# PCB_Agrosavia.net
KiCad netlist of a schematic drawn in EAGLE
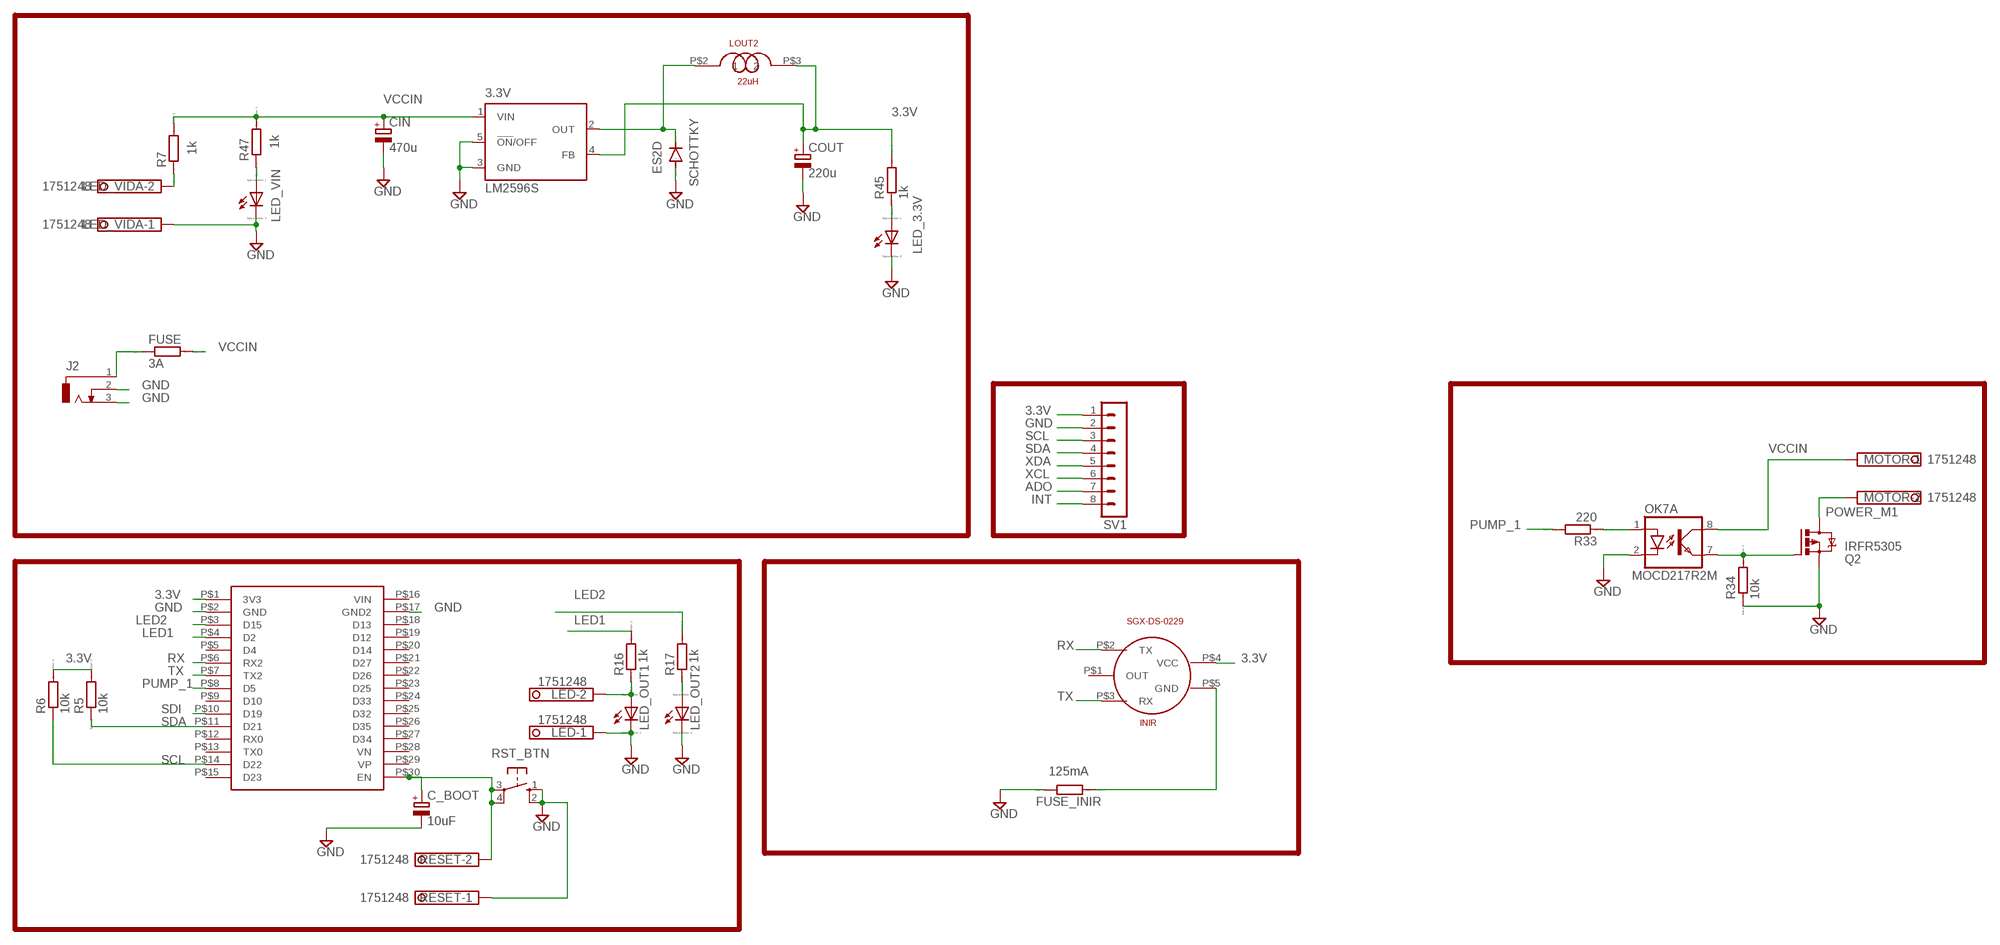
[diagram p0: schematic, sheet 1]

(export (version "E")
  (design (tool "Eeschema 10.0.6"))
  (components
    (comp (ref "3.3V")
      (value "LM2596S")
      (footprint "eagle-import:TO263-5")
      (fields (field (name "MF") "NATIONAL SEMICONDUCTOR") (field (name "MPN") "LM2596S-ADJ/NOPB"))
      (libsource (lib "eagle-import") (part "LM2596S"))
    )
    (comp (ref "CIN")
      (value "470u")
      (footprint "eagle-import:SANYO-OSCON_SMD_F12")
      (libsource (lib "eagle-import") (part "CPOL-EUSANYO_SMD_F12"))
    )
    (comp (ref "COUT")
      (value "220u")
      (footprint "eagle-import:UD-10X10_NICHICON")
      (libsource (lib "eagle-import") (part "CPOL-EUUD-10X10"))
    )
    (comp (ref "C_BOOT")
      (value "10uF")
      (footprint "eagle-import:SANYO-OSCON_SMD_B6")
      (libsource (lib "eagle-import") (part "CPOL-EUSANYO_SMD_B6"))
    )
    (comp (ref "ESP32DEVKITV1")
      (value "ESP32")
      (footprint "eagle-import:ESP32")
      (libsource (lib "eagle-import") (part "ESP32"))
    )
    (comp (ref "FUSE")
      (value "3A")
      (footprint "eagle-import:R1206")
      (libsource (lib "eagle-import") (part "RR1206"))
    )
    (comp (ref "FUSE_INIR")
      (value "125mA")
      (footprint "eagle-import:R0402")
      (libsource (lib "eagle-import") (part "RR0402"))
    )
    (comp (ref "J2")
      (value "DCJ0303")
      (footprint "eagle-import:DCJ0303")
      (libsource (lib "eagle-import") (part "DCJ0303"))
    )
    (comp (ref "LED")
      (value "1751248")
      (footprint "eagle-import:1751248")
      (libsource (lib "eagle-import") (part "1751248"))
    )
    (comp (ref "LED_3.3V")
      (value "LED_E")
      (footprint "eagle-import:LED_1206")
      (libsource (lib "eagle-import") (part "LED_E"))
    )
    (comp (ref "LED_OUT1")
      (value "LED_E")
      (footprint "eagle-import:LED_1206")
      (libsource (lib "eagle-import") (part "LED_E"))
    )
    (comp (ref "LED_OUT2")
      (value "LED_E")
      (footprint "eagle-import:LED_1206")
      (libsource (lib "eagle-import") (part "LED_E"))
    )
    (comp (ref "LED_VIDA")
      (value "1751248")
      (footprint "eagle-import:1751248")
      (libsource (lib "eagle-import") (part "1751248"))
    )
    (comp (ref "LED_VIN")
      (value "LED_E")
      (footprint "eagle-import:LED_1206")
      (libsource (lib "eagle-import") (part "LED_E"))
    )
    (comp (ref "LOUT2")
      (value "22uH")
      (footprint "eagle-import:SRP1038A")
      (libsource (lib "eagle-import") (part "SRP1038A"))
    )
    (comp (ref "MOTOR")
      (value "1751248")
      (footprint "eagle-import:1751248")
      (libsource (lib "eagle-import") (part "1751248"))
    )
    (comp (ref "OK7")
      (value "MOCD217R2M")
      (footprint "eagle-import:SOIC08")
      (fields (field (name "MF") "VISHAY/TELEFUNKEN") (field (name "MPN") "ILD205T"))
      (libsource (lib "eagle-import") (part "ILD205"))
    )
    (comp (ref "Q2")
      (value "IRFR5305")
      (footprint "eagle-import:D-PAK_TO252AA")
      (libsource (lib "eagle-import") (part "IRF?5305R"))
    )
    (comp (ref "R5")
      (value "10k")
      (footprint "eagle-import:R1206")
      (libsource (lib "eagle-import") (part "RR1206"))
    )
    (comp (ref "R6")
      (value "10k")
      (footprint "eagle-import:R1206")
      (libsource (lib "eagle-import") (part "RR1206"))
    )
    (comp (ref "R7")
      (value "1k")
      (footprint "eagle-import:R0805")
      (libsource (lib "eagle-import") (part "R"))
    )
    (comp (ref "R16")
      (value "1k")
      (footprint "eagle-import:R0805")
      (libsource (lib "eagle-import") (part "R"))
    )
    (comp (ref "R17")
      (value "1k")
      (footprint "eagle-import:R0805")
      (libsource (lib "eagle-import") (part "R"))
    )
    (comp (ref "R33")
      (value "220")
      (footprint "eagle-import:R0603")
      (libsource (lib "eagle-import") (part "RR0603"))
    )
    (comp (ref "R34")
      (value "10k")
      (footprint "eagle-import:R1206")
      (libsource (lib "eagle-import") (part "RR1206"))
    )
    (comp (ref "R45")
      (value "1k")
      (footprint "eagle-import:R0805")
      (libsource (lib "eagle-import") (part "R"))
    )
    (comp (ref "R47")
      (value "1k")
      (footprint "eagle-import:R0805")
      (libsource (lib "eagle-import") (part "R"))
    )
    (comp (ref "RESET")
      (value "1751248")
      (footprint "eagle-import:1751248")
      (libsource (lib "eagle-import") (part "1751248"))
    )
    (comp (ref "RST_BTN")
      (value "10-XX")
      (footprint "eagle-import:B3F-10XX")
      (fields (field (name "MPN") "B3F-1000"))
      (libsource (lib "eagle-import") (part "10-XX"))
    )
    (comp (ref "SCHOTTKY")
      (value "ES2D")
      (footprint "eagle-import:SMB")
      (libsource (lib "eagle-import") (part "ES2D"))
    )
    (comp (ref "SGX-DS-0229")
      (value "INIR")
      (footprint "eagle-import:INIR")
      (libsource (lib "eagle-import") (part "INIR"))
    )
    (comp (ref "SV1")
      (value "MA08-1")
      (footprint "eagle-import:MA08-1")
      (libsource (lib "eagle-import") (part "MA08-1"))
    )
  )
  (nets
    (net (code "1") (name "/3.3V") (class "Default")
      (node (ref "3.3V") (pin "4") (pinfunction "FB_4") (pintype "input"))
      (node (ref "COUT") (pin "+") (pinfunction "+_+") (pintype "passive"))
      (node (ref "ESP32DEVKITV1") (pin "P$1") (pinfunction "3V3_P$1") (pintype "bidirectional"))
      (node (ref "LOUT2") (pin "P$3") (pinfunction "2_P$3") (pintype "bidirectional"))
      (node (ref "R45") (pin "2") (pinfunction "2_2") (pintype "passive"))
      (node (ref "R5") (pin "2") (pinfunction "2_2") (pintype "passive"))
      (node (ref "R6") (pin "2") (pinfunction "2_2") (pintype "passive"))
      (node (ref "SGX-DS-0229") (pin "P$4") (pinfunction "VCC_P$4") (pintype "bidirectional"))
      (node (ref "SV1") (pin "1") (pinfunction "1_1") (pintype "passive"))
    )
    (net (code "2") (name "/ADO") (class "Default")
      (node (ref "SV1") (pin "7") (pinfunction "7_7") (pintype "passive"))
    )
    (net (code "3") (name "/INT") (class "Default")
      (node (ref "SV1") (pin "8") (pinfunction "8_8") (pintype "passive"))
    )
    (net (code "4") (name "/LED1") (class "Default")
      (node (ref "ESP32DEVKITV1") (pin "P$4") (pinfunction "D2_P$4") (pintype "bidirectional"))
      (node (ref "R16") (pin "2") (pinfunction "2_2") (pintype "passive"))
    )
    (net (code "5") (name "/LED2") (class "Default")
      (node (ref "ESP32DEVKITV1") (pin "P$3") (pinfunction "D15_P$3") (pintype "bidirectional"))
      (node (ref "R17") (pin "2") (pinfunction "2_2") (pintype "passive"))
    )
    (net (code "6") (name "/POWER_M1") (class "Default")
      (node (ref "MOTOR") (pin "2") (pinfunction "K_2") (pintype "passive"))
      (node (ref "Q2") (pin "4") (pinfunction "D_4") (pintype "passive"))
    )
    (net (code "7") (name "/PUMP_1") (class "Default")
      (node (ref "ESP32DEVKITV1") (pin "P$8") (pinfunction "D5_P$8") (pintype "bidirectional"))
      (node (ref "R33") (pin "2") (pinfunction "2_2") (pintype "passive"))
    )
    (net (code "8") (name "/RX") (class "Default")
      (node (ref "ESP32DEVKITV1") (pin "P$6") (pinfunction "RX2_P$6") (pintype "bidirectional"))
      (node (ref "SGX-DS-0229") (pin "P$2") (pinfunction "TX_P$2") (pintype "bidirectional"))
    )
    (net (code "9") (name "/SCL") (class "Default")
      (node (ref "ESP32DEVKITV1") (pin "P$14") (pinfunction "D22_P$14") (pintype "bidirectional"))
      (node (ref "R6") (pin "1") (pinfunction "1_1") (pintype "passive"))
      (node (ref "SV1") (pin "3") (pinfunction "3_3") (pintype "passive"))
    )
    (net (code "10") (name "/SDA") (class "Default")
      (node (ref "ESP32DEVKITV1") (pin "P$11") (pinfunction "D21_P$11") (pintype "bidirectional"))
      (node (ref "R5") (pin "1") (pinfunction "1_1") (pintype "passive"))
      (node (ref "SV1") (pin "4") (pinfunction "4_4") (pintype "passive"))
    )
    (net (code "11") (name "/SDI") (class "Default")
      (node (ref "ESP32DEVKITV1") (pin "P$10") (pinfunction "D19_P$10") (pintype "bidirectional"))
    )
    (net (code "12") (name "/TX") (class "Default")
      (node (ref "ESP32DEVKITV1") (pin "P$7") (pinfunction "TX2_P$7") (pintype "bidirectional"))
      (node (ref "SGX-DS-0229") (pin "P$3") (pinfunction "RX_P$3") (pintype "bidirectional"))
    )
    (net (code "13") (name "/VCCIN") (class "Default")
      (node (ref "3.3V") (pin "1") (pinfunction "VIN_1") (pintype "input"))
      (node (ref "CIN") (pin "+") (pinfunction "+_+") (pintype "passive"))
      (node (ref "FUSE") (pin "2") (pinfunction "2_2") (pintype "passive"))
      (node (ref "MOTOR") (pin "1") (pinfunction "K_1") (pintype "passive"))
      (node (ref "OK7") (pin "8") (pinfunction "COL_8") (pintype "passive"))
      (node (ref "R47") (pin "2") (pinfunction "2_2") (pintype "passive"))
      (node (ref "R7") (pin "2") (pinfunction "2_2") (pintype "passive"))
    )
    (net (code "14") (name "/XCL") (class "Default")
      (node (ref "SV1") (pin "6") (pinfunction "6_6") (pintype "passive"))
    )
    (net (code "15") (name "/XDA") (class "Default")
      (node (ref "SV1") (pin "5") (pinfunction "5_5") (pintype "passive"))
    )
    (net (code "16") (name "GND") (class "Default")
      (node (ref "3.3V") (pin "3") (pinfunction "GND_3") (pintype "power_in"))
      (node (ref "3.3V") (pin "5") (pinfunction "~{ON}/OFF_5") (pintype "input"))
      (node (ref "CIN") (pin "-") (pinfunction "-_-") (pintype "passive"))
      (node (ref "COUT") (pin "-") (pinfunction "-_-") (pintype "passive"))
      (node (ref "C_BOOT") (pin "-") (pinfunction "-_-") (pintype "passive"))
      (node (ref "ESP32DEVKITV1") (pin "P$17") (pinfunction "GND2_P$17") (pintype "bidirectional"))
      (node (ref "ESP32DEVKITV1") (pin "P$2") (pinfunction "GND_P$2") (pintype "bidirectional"))
      (node (ref "FUSE_INIR") (pin "2") (pinfunction "2_2") (pintype "passive"))
      (node (ref "J2") (pin "2") (pinfunction "2_2") (pintype "passive"))
      (node (ref "J2") (pin "3") (pinfunction "3_3") (pintype "passive"))
      (node (ref "LED") (pin "1") (pinfunction "K_1") (pintype "passive"))
      (node (ref "LED_3.3V") (pin "C") (pinfunction "C_C") (pintype "passive"))
      (node (ref "LED_OUT1") (pin "C") (pinfunction "C_C") (pintype "passive"))
      (node (ref "LED_OUT2") (pin "C") (pinfunction "C_C") (pintype "passive"))
      (node (ref "LED_VIDA") (pin "1") (pinfunction "K_1") (pintype "passive"))
      (node (ref "LED_VIN") (pin "C") (pinfunction "C_C") (pintype "passive"))
      (node (ref "OK7") (pin "2") (pinfunction "C_2") (pintype "passive"))
      (node (ref "Q2") (pin "3") (pinfunction "S_3") (pintype "passive"))
      (node (ref "R34") (pin "1") (pinfunction "1_1") (pintype "passive"))
      (node (ref "RESET") (pin "1") (pinfunction "K_1") (pintype "passive"))
      (node (ref "RST_BTN") (pin "1") (pinfunction "S_1") (pintype "passive"))
      (node (ref "RST_BTN") (pin "2") (pinfunction "S1_2") (pintype "passive"))
      (node (ref "SCHOTTKY") (pin "A") (pinfunction "A_A") (pintype "passive"))
      (node (ref "SV1") (pin "2") (pinfunction "2_2") (pintype "passive"))
    )
    (net (code "17") (name "Net-(3.3V-OUT)") (class "Default")
      (node (ref "3.3V") (pin "2") (pinfunction "OUT_2") (pintype "output"))
      (node (ref "LOUT2") (pin "P$2") (pinfunction "1_P$2") (pintype "bidirectional"))
      (node (ref "SCHOTTKY") (pin "C") (pinfunction "C_C") (pintype "passive"))
    )
    (net (code "18") (name "Net-(ESP32DEVKITV1-EN)") (class "Default")
      (node (ref "C_BOOT") (pin "+") (pinfunction "+_+") (pintype "passive"))
      (node (ref "ESP32DEVKITV1") (pin "P$30") (pinfunction "EN_P$30") (pintype "bidirectional"))
      (node (ref "RESET") (pin "2") (pinfunction "K_2") (pintype "passive"))
      (node (ref "RST_BTN") (pin "3") (pinfunction "P_3") (pintype "passive"))
      (node (ref "RST_BTN") (pin "4") (pinfunction "P1_4") (pintype "passive"))
    )
    (net (code "19") (name "Net-(FUSE-Pad1)") (class "Default")
      (node (ref "FUSE") (pin "1") (pinfunction "1_1") (pintype "passive"))
      (node (ref "J2") (pin "1") (pinfunction "1_1") (pintype "passive"))
    )
    (net (code "20") (name "Net-(LEDB-K)") (class "Default")
      (node (ref "LED") (pin "2") (pinfunction "K_2") (pintype "passive"))
      (node (ref "LED_OUT1") (pin "A") (pinfunction "A_A") (pintype "passive"))
      (node (ref "R16") (pin "1") (pinfunction "1_1") (pintype "passive"))
    )
    (net (code "21") (name "Net-(LED_3.3V-PadA)") (class "Default")
      (node (ref "LED_3.3V") (pin "A") (pinfunction "A_A") (pintype "passive"))
      (node (ref "R45") (pin "1") (pinfunction "1_1") (pintype "passive"))
    )
    (net (code "22") (name "Net-(LED_OUT2-PadA)") (class "Default")
      (node (ref "LED_OUT2") (pin "A") (pinfunction "A_A") (pintype "passive"))
      (node (ref "R17") (pin "1") (pinfunction "1_1") (pintype "passive"))
    )
    (net (code "23") (name "Net-(LED_VIDAB-K)") (class "Default")
      (node (ref "LED_VIDA") (pin "2") (pinfunction "K_2") (pintype "passive"))
      (node (ref "R7") (pin "1") (pinfunction "1_1") (pintype "passive"))
    )
    (net (code "24") (name "Net-(LED_VIN-PadA)") (class "Default")
      (node (ref "LED_VIN") (pin "A") (pinfunction "A_A") (pintype "passive"))
      (node (ref "R47") (pin "1") (pinfunction "1_1") (pintype "passive"))
    )
    (net (code "25") (name "Net-(OK7A-A)") (class "Default")
      (node (ref "OK7") (pin "1") (pinfunction "A_1") (pintype "passive"))
      (node (ref "R33") (pin "1") (pinfunction "1_1") (pintype "passive"))
    )
    (net (code "26") (name "Net-(OK7A-EMIT)") (class "Default")
      (node (ref "OK7") (pin "7") (pinfunction "EMIT_7") (pintype "passive"))
      (node (ref "Q2") (pin "1") (pinfunction "G_1") (pintype "passive"))
      (node (ref "R34") (pin "2") (pinfunction "2_2") (pintype "passive"))
    )
    (net (code "27") (name "Net-(SGX-DS-0229-GND)") (class "Default")
      (node (ref "FUSE_INIR") (pin "1") (pinfunction "1_1") (pintype "passive"))
      (node (ref "SGX-DS-0229") (pin "P$5") (pinfunction "GND_P$5") (pintype "bidirectional"))
    )
    (net (code "28") (name "unconnected-(ESP32DEVKITV1-D4-PadP$5)") (class "Default")
      (node (ref "ESP32DEVKITV1") (pin "P$5") (pinfunction "D4_P$5") (pintype "bidirectional"))
    )
    (net (code "29") (name "unconnected-(ESP32DEVKITV1-D10-PadP$9)") (class "Default")
      (node (ref "ESP32DEVKITV1") (pin "P$9") (pinfunction "D10_P$9") (pintype "bidirectional"))
    )
    (net (code "30") (name "unconnected-(ESP32DEVKITV1-D12-PadP$19)") (class "Default")
      (node (ref "ESP32DEVKITV1") (pin "P$19") (pinfunction "D12_P$19") (pintype "bidirectional"))
    )
    (net (code "31") (name "unconnected-(ESP32DEVKITV1-D13-PadP$18)") (class "Default")
      (node (ref "ESP32DEVKITV1") (pin "P$18") (pinfunction "D13_P$18") (pintype "bidirectional"))
    )
    (net (code "32") (name "unconnected-(ESP32DEVKITV1-D14-PadP$20)") (class "Default")
      (node (ref "ESP32DEVKITV1") (pin "P$20") (pinfunction "D14_P$20") (pintype "bidirectional"))
    )
    (net (code "33") (name "unconnected-(ESP32DEVKITV1-D23-PadP$15)") (class "Default")
      (node (ref "ESP32DEVKITV1") (pin "P$15") (pinfunction "D23_P$15") (pintype "bidirectional"))
    )
    (net (code "34") (name "unconnected-(ESP32DEVKITV1-D25-PadP$23)") (class "Default")
      (node (ref "ESP32DEVKITV1") (pin "P$23") (pinfunction "D25_P$23") (pintype "bidirectional"))
    )
    (net (code "35") (name "unconnected-(ESP32DEVKITV1-D26-PadP$22)") (class "Default")
      (node (ref "ESP32DEVKITV1") (pin "P$22") (pinfunction "D26_P$22") (pintype "bidirectional"))
    )
    (net (code "36") (name "unconnected-(ESP32DEVKITV1-D27-PadP$21)") (class "Default")
      (node (ref "ESP32DEVKITV1") (pin "P$21") (pinfunction "D27_P$21") (pintype "bidirectional"))
    )
    (net (code "37") (name "unconnected-(ESP32DEVKITV1-D32-PadP$25)") (class "Default")
      (node (ref "ESP32DEVKITV1") (pin "P$25") (pinfunction "D32_P$25") (pintype "bidirectional"))
    )
    (net (code "38") (name "unconnected-(ESP32DEVKITV1-D33-PadP$24)") (class "Default")
      (node (ref "ESP32DEVKITV1") (pin "P$24") (pinfunction "D33_P$24") (pintype "bidirectional"))
    )
    (net (code "39") (name "unconnected-(ESP32DEVKITV1-D34-PadP$27)") (class "Default")
      (node (ref "ESP32DEVKITV1") (pin "P$27") (pinfunction "D34_P$27") (pintype "bidirectional"))
    )
    (net (code "40") (name "unconnected-(ESP32DEVKITV1-D35-PadP$26)") (class "Default")
      (node (ref "ESP32DEVKITV1") (pin "P$26") (pinfunction "D35_P$26") (pintype "bidirectional"))
    )
    (net (code "41") (name "unconnected-(ESP32DEVKITV1-RX0-PadP$12)") (class "Default")
      (node (ref "ESP32DEVKITV1") (pin "P$12") (pinfunction "RX0_P$12") (pintype "bidirectional"))
    )
    (net (code "42") (name "unconnected-(ESP32DEVKITV1-TX0-PadP$13)") (class "Default")
      (node (ref "ESP32DEVKITV1") (pin "P$13") (pinfunction "TX0_P$13") (pintype "bidirectional"))
    )
    (net (code "43") (name "unconnected-(ESP32DEVKITV1-VIN-PadP$16)") (class "Default")
      (node (ref "ESP32DEVKITV1") (pin "P$16") (pinfunction "VIN_P$16") (pintype "bidirectional"))
    )
    (net (code "44") (name "unconnected-(ESP32DEVKITV1-VN-PadP$28)") (class "Default")
      (node (ref "ESP32DEVKITV1") (pin "P$28") (pinfunction "VN_P$28") (pintype "bidirectional"))
    )
    (net (code "45") (name "unconnected-(ESP32DEVKITV1-VP-PadP$29)") (class "Default")
      (node (ref "ESP32DEVKITV1") (pin "P$29") (pinfunction "VP_P$29") (pintype "bidirectional"))
    )
    (net (code "46") (name "unconnected-(SGX-DS-0229-OUT-PadP$1)") (class "Default")
      (node (ref "SGX-DS-0229") (pin "P$1") (pinfunction "OUT_P$1") (pintype "bidirectional"))
    )
  )
)
